# CircuitoControle.net
KiCad netlist of a schematic drawn in Altium Designer
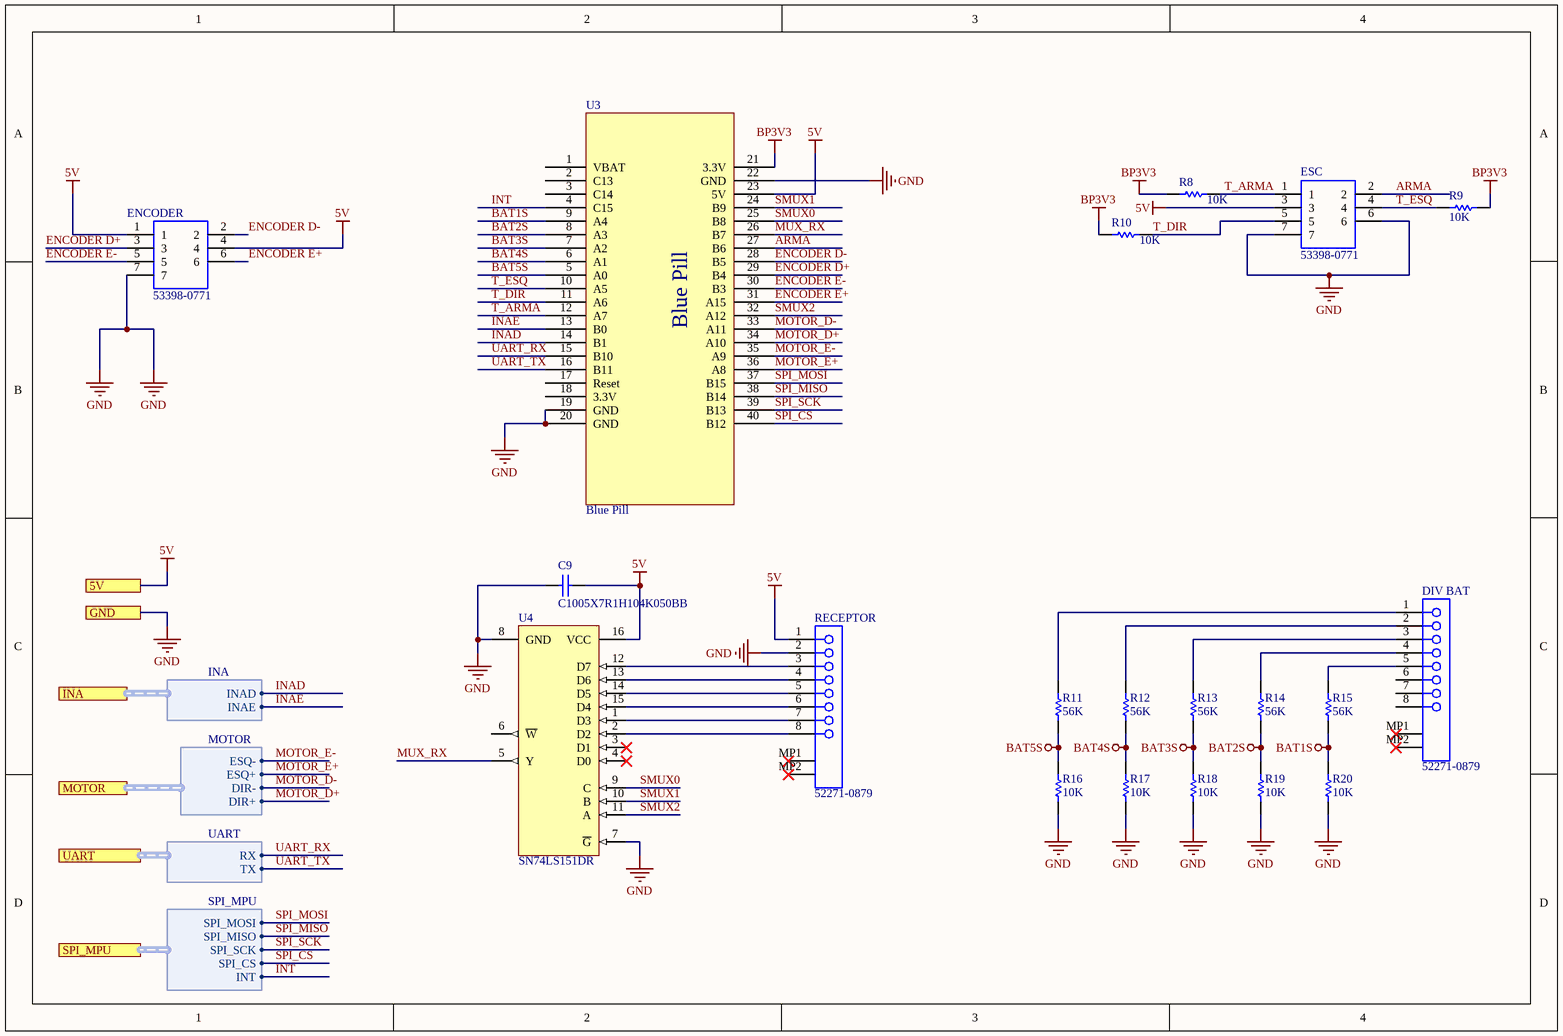
[diagram p0: CircuitoControle.SchDoc]

(export (version "E")
  (design (tool "Eeschema 10.0.6"))
  (components
    (comp (ref "C9")
      (value "C1005X7R1H104K050BB")
      (footprint "TDK-C1005-2_M")
      (description "Chip Capacitor, 0.1 uF, +/- 10%, 50 V, -55 to 125 degC, 0402(1005 Metric), RoHS, Tape and Reel")
      (fields
        (field (name "PCN PART NUMBER") "MLCCPartNumberChange30/Nov/2012")
        (field (name "TOLERANCE") "±10%")
      )
      (libsource (lib "Altium Content Vault") (part "CAP-NP-2"))
    )
    (comp (ref "DIV BAT")
      (value "52271-0879")
      (footprint "MOLX-52271-0879")
      (fields (field (name "MANUFACTURER") "Molex"))
      (libsource (lib "Altium Content Vault") (part "MOLX-52271-0879"))
    )
    (comp (ref "ENCODER")
      (value "53398-0771")
      (footprint "53398-0771:53398-0771")
      (fields (field (name "RS PART NUMBER") "5427220P"))
      (libsource (lib "53398-0771") (part "53398-0771"))
    )
    (comp (ref "ESC")
      (value "53398-0771")
      (footprint "53398-0771")
      (fields (field (name "RS PART NUMBER") "5427220P"))
      (libsource (lib "53398-0771") (part "53398-0771"))
    )
    (comp (ref "R8")
      (value "10K")
      (footprint "RESC0402(1005)_L")
      (description "10K 0.063W 1% 0402 (1005 Metric)  SMD")
      (fields (field (name "TOLERANCE") "1 %") (field (name "POWER") "0.063 W"))
      (libsource (lib "Resistor 0402 10K") (part "CMP-1011-00623-1"))
    )
    (comp (ref "R9")
      (value "10K")
      (footprint "RESC0402(1005)_L")
      (description "10K 0.063W 1% 0402 (1005 Metric)  SMD")
      (fields (field (name "TOLERANCE") "1 %") (field (name "POWER") "0.063 W"))
      (libsource (lib "Resistor 0402 10K") (part "CMP-1011-00623-1"))
    )
    (comp (ref "R10")
      (value "10K")
      (footprint "RESC0402(1005)_L")
      (description "10K 0.063W 1% 0402 (1005 Metric)  SMD")
      (fields (field (name "TOLERANCE") "1 %") (field (name "POWER") "0.063 W"))
      (libsource (lib "Resistor 0402 10K") (part "CMP-1011-00623-1"))
    )
    (comp (ref "R11")
      (value "56K")
      (footprint "RESC0402(1005)_N")
      (description "56K 0.063W 1% 0402 (1005 Metric)  SMD")
      (fields (field (name "TOLERANCE") "1 %") (field (name "POWER") "0.063 W"))
      (libsource (lib "Altium Content Vault") (part "RES"))
    )
    (comp (ref "R12")
      (value "56K")
      (footprint "RESC0402(1005)_N")
      (description "56K 0.063W 1% 0402 (1005 Metric)  SMD")
      (fields (field (name "TOLERANCE") "1 %") (field (name "POWER") "0.063 W"))
      (libsource (lib "Altium Content Vault") (part "RES"))
    )
    (comp (ref "R13")
      (value "56K")
      (footprint "RESC0402(1005)_N")
      (description "56K 0.063W 1% 0402 (1005 Metric)  SMD")
      (fields (field (name "TOLERANCE") "1 %") (field (name "POWER") "0.063 W"))
      (libsource (lib "Altium Content Vault") (part "RES"))
    )
    (comp (ref "R14")
      (value "56K")
      (footprint "RESC0402(1005)_N")
      (description "56K 0.063W 1% 0402 (1005 Metric)  SMD")
      (fields (field (name "TOLERANCE") "1 %") (field (name "POWER") "0.063 W"))
      (libsource (lib "Altium Content Vault") (part "RES"))
    )
    (comp (ref "R15")
      (value "56K")
      (footprint "RESC0402(1005)_N")
      (description "56K 0.063W 1% 0402 (1005 Metric)  SMD")
      (fields (field (name "TOLERANCE") "1 %") (field (name "POWER") "0.063 W"))
      (libsource (lib "Altium Content Vault") (part "RES"))
    )
    (comp (ref "R16")
      (value "10K")
      (footprint "RESC0402(1005)_L")
      (description "10K 0.063W 1% 0402 (1005 Metric)  SMD")
      (fields (field (name "TOLERANCE") "1 %") (field (name "POWER") "0.063 W"))
      (libsource (lib "Resistor 0402 10K") (part "CMP-1011-00623-1"))
    )
    (comp (ref "R17")
      (value "10K")
      (footprint "RESC0402(1005)_L")
      (description "10K 0.063W 1% 0402 (1005 Metric)  SMD")
      (fields (field (name "TOLERANCE") "1 %") (field (name "POWER") "0.063 W"))
      (libsource (lib "Resistor 0402 10K") (part "CMP-1011-00623-1"))
    )
    (comp (ref "R18")
      (value "10K")
      (footprint "RESC0402(1005)_L")
      (description "10K 0.063W 1% 0402 (1005 Metric)  SMD")
      (fields (field (name "TOLERANCE") "1 %") (field (name "POWER") "0.063 W"))
      (libsource (lib "Resistor 0402 10K") (part "CMP-1011-00623-1"))
    )
    (comp (ref "R19")
      (value "10K")
      (footprint "RESC0402(1005)_L")
      (description "10K 0.063W 1% 0402 (1005 Metric)  SMD")
      (fields (field (name "TOLERANCE") "1 %") (field (name "POWER") "0.063 W"))
      (libsource (lib "Resistor 0402 10K") (part "CMP-1011-00623-1"))
    )
    (comp (ref "R20")
      (value "10K")
      (footprint "RESC0402(1005)_L")
      (description "10K 0.063W 1% 0402 (1005 Metric)  SMD")
      (fields (field (name "TOLERANCE") "1 %") (field (name "POWER") "0.063 W"))
      (libsource (lib "Resistor 0402 10K") (part "CMP-1011-00623-1"))
    )
    (comp (ref "RECEPTOR")
      (value "52271-0879")
      (footprint "MOLX-52271-0879")
      (fields (field (name "MANUFACTURER") "Molex"))
      (libsource (lib "Altium Content Vault") (part "MOLX-52271-0879"))
    )
    (comp (ref "U3")
      (value "Blue Pill")
      (footprint "sAMACsYS:blue pill")
      (libsource (lib "Schlib1") (part "Blue Pill"))
    )
    (comp (ref "U4")
      (value "SN74LS151DR")
      (footprint "D0016A_L")
      (description "8-Line To 1-Line Data Selectors/Multiplexers, D0016A, LARGE T&R")
      (fields
        (field (name "MANUFACTURER") "Texas Instruments")
        (field (name "GENERIC PART NUMBER") "SN74LS151")
      )
      (libsource (lib "mux SN74LS151DR") (part "CMP-1633-00148-1"))
    )
  )
  (nets
    (net (code "6") (name "/ARMA") (class "Default")
      (node (ref "ESC") (pin "2") (pinfunction "2_2") (pintype "passive"))
      (node (ref "U3") (pin "27") (pinfunction "B6_27") (pintype "passive"))
    )
    (net (code "7") (name "/ENCODER D+") (class "Default")
      (node (ref "ENCODER") (pin "3") (pinfunction "3_3") (pintype "passive"))
      (node (ref "U3") (pin "29") (pinfunction "B4_29") (pintype "passive"))
    )
    (net (code "8") (name "/ENCODER D-") (class "Default")
      (node (ref "ENCODER") (pin "2") (pinfunction "2_2") (pintype "passive"))
      (node (ref "U3") (pin "28") (pinfunction "B5_28") (pintype "passive"))
    )
    (net (code "9") (name "/ENCODER E+") (class "Default")
      (node (ref "ENCODER") (pin "6") (pinfunction "6_6") (pintype "passive"))
      (node (ref "U3") (pin "31") (pinfunction "A15_31") (pintype "passive"))
    )
    (net (code "10") (name "/ENCODER E-") (class "Default")
      (node (ref "ENCODER") (pin "5") (pinfunction "5_5") (pintype "passive"))
      (node (ref "U3") (pin "30") (pinfunction "B3_30") (pintype "passive"))
    )
    (net (code "11") (name "/INAD") (class "Default")
      (node (ref "U3") (pin "14") (pinfunction "B1_14") (pintype "passive"))
    )
    (net (code "12") (name "/INAE") (class "Default")
      (node (ref "U3") (pin "13") (pinfunction "B0_13") (pintype "passive"))
    )
    (net (code "13") (name "/INT") (class "Default")
      (node (ref "U3") (pin "4") (pinfunction "C15_4") (pintype "passive"))
    )
    (net (code "14") (name "/MOTOR_D+") (class "Default")
      (node (ref "U3") (pin "34") (pinfunction "A10_34") (pintype "passive"))
    )
    (net (code "15") (name "/MOTOR_D-") (class "Default")
      (node (ref "U3") (pin "33") (pinfunction "A11_33") (pintype "passive"))
    )
    (net (code "16") (name "/MOTOR_E+") (class "Default")
      (node (ref "U3") (pin "36") (pinfunction "A8_36") (pintype "passive"))
    )
    (net (code "17") (name "/MOTOR_E-") (class "Default")
      (node (ref "U3") (pin "35") (pinfunction "A9_35") (pintype "passive"))
    )
    (net (code "18") (name "/MUX_RX") (class "Default")
      (node (ref "U3") (pin "26") (pinfunction "B7_26") (pintype "passive"))
      (node (ref "U4") (pin "5") (pinfunction "Y_5") (pintype "output"))
    )
    (net (code "19") (name "/SMUX0") (class "Default")
      (node (ref "U3") (pin "25") (pinfunction "B8_25") (pintype "passive"))
      (node (ref "U4") (pin "9") (pinfunction "C_9") (pintype "input"))
    )
    (net (code "20") (name "/SMUX1") (class "Default")
      (node (ref "U3") (pin "24") (pinfunction "B9_24") (pintype "passive"))
      (node (ref "U4") (pin "10") (pinfunction "B_10") (pintype "input"))
    )
    (net (code "21") (name "/SMUX2") (class "Default")
      (node (ref "U3") (pin "32") (pinfunction "A12_32") (pintype "passive"))
      (node (ref "U4") (pin "11") (pinfunction "A_11") (pintype "input"))
    )
    (net (code "22") (name "/SPI_CS") (class "Default")
      (node (ref "U3") (pin "40") (pinfunction "B12_40") (pintype "passive"))
    )
    (net (code "23") (name "/SPI_MISO") (class "Default")
      (node (ref "U3") (pin "38") (pinfunction "B14_38") (pintype "passive"))
    )
    (net (code "24") (name "/SPI_MOSI") (class "Default")
      (node (ref "U3") (pin "37") (pinfunction "B15_37") (pintype "passive"))
    )
    (net (code "25") (name "/SPI_SCK") (class "Default")
      (node (ref "U3") (pin "39") (pinfunction "B13_39") (pintype "passive"))
    )
    (net (code "26") (name "/T_ARMA") (class "Default")
      (node (ref "ESC") (pin "1") (pinfunction "1_1") (pintype "passive"))
      (node (ref "R8") (pin "1") (pinfunction "1_1") (pintype "passive"))
      (node (ref "U3") (pin "12") (pinfunction "A7_12") (pintype "passive"))
    )
    (net (code "27") (name "/T_DIR") (class "Default")
      (node (ref "ESC") (pin "5") (pinfunction "5_5") (pintype "passive"))
      (node (ref "R10") (pin "1") (pinfunction "1_1") (pintype "passive"))
      (node (ref "U3") (pin "11") (pinfunction "A6_11") (pintype "passive"))
    )
    (net (code "28") (name "/T_ESQ") (class "Default")
      (node (ref "ESC") (pin "4") (pinfunction "4_4") (pintype "passive"))
      (node (ref "R9") (pin "2") (pinfunction "2_2") (pintype "passive"))
      (node (ref "U3") (pin "10") (pinfunction "A5_10") (pintype "passive"))
    )
    (net (code "29") (name "/UART_RX") (class "Default")
      (node (ref "U3") (pin "15") (pinfunction "B10_15") (pintype "passive"))
    )
    (net (code "30") (name "/UART_TX") (class "Default")
      (node (ref "U3") (pin "16") (pinfunction "B11_16") (pintype "passive"))
    )
    (net (code "35") (name "5V") (class "Default")
      (node (ref "C9") (pin "2") (pinfunction "2_2") (pintype "passive"))
      (node (ref "ENCODER") (pin "1") (pinfunction "1_1") (pintype "passive"))
      (node (ref "ENCODER") (pin "4") (pinfunction "4_4") (pintype "passive"))
      (node (ref "ESC") (pin "3") (pinfunction "3_3") (pintype "passive"))
      (node (ref "RECEPTOR") (pin "1") (pinfunction "1_1") (pintype "passive"))
      (node (ref "U3") (pin "23") (pinfunction "5V_23") (pintype "passive"))
      (node (ref "U4") (pin "16") (pinfunction "VCC_16") (pintype "power_in"))
    )
    (net (code "36") (name "BAT1S") (class "Default")
      (node (ref "R15") (pin "1") (pinfunction "1_1") (pintype "passive"))
      (node (ref "R20") (pin "2") (pinfunction "2_2") (pintype "passive"))
      (node (ref "U3") (pin "9") (pinfunction "A4_9") (pintype "passive"))
    )
    (net (code "37") (name "BAT2S") (class "Default")
      (node (ref "R14") (pin "1") (pinfunction "1_1") (pintype "passive"))
      (node (ref "R19") (pin "2") (pinfunction "2_2") (pintype "passive"))
      (node (ref "U3") (pin "8") (pinfunction "A3_8") (pintype "passive"))
    )
    (net (code "38") (name "BAT3S") (class "Default")
      (node (ref "R13") (pin "1") (pinfunction "1_1") (pintype "passive"))
      (node (ref "R18") (pin "2") (pinfunction "2_2") (pintype "passive"))
      (node (ref "U3") (pin "7") (pinfunction "A2_7") (pintype "passive"))
    )
    (net (code "39") (name "BAT4S") (class "Default")
      (node (ref "R12") (pin "1") (pinfunction "1_1") (pintype "passive"))
      (node (ref "R17") (pin "2") (pinfunction "2_2") (pintype "passive"))
      (node (ref "U3") (pin "6") (pinfunction "A1_6") (pintype "passive"))
    )
    (net (code "40") (name "BAT5S") (class "Default")
      (node (ref "R11") (pin "1") (pinfunction "1_1") (pintype "passive"))
      (node (ref "R16") (pin "2") (pinfunction "2_2") (pintype "passive"))
      (node (ref "U3") (pin "5") (pinfunction "A0_5") (pintype "passive"))
    )
    (net (code "41") (name "BP3V3") (class "Default")
      (node (ref "R10") (pin "2") (pinfunction "2_2") (pintype "passive"))
      (node (ref "R8") (pin "2") (pinfunction "2_2") (pintype "passive"))
      (node (ref "R9") (pin "1") (pinfunction "1_1") (pintype "passive"))
      (node (ref "U3") (pin "21") (pinfunction "3.3V_21") (pintype "passive"))
    )
    (net (code "42") (name "GND") (class "Default")
      (node (ref "C9") (pin "1") (pinfunction "1_1") (pintype "passive"))
      (node (ref "ENCODER") (pin "7") (pinfunction "7_7") (pintype "passive"))
      (node (ref "ESC") (pin "6") (pinfunction "6_6") (pintype "passive"))
      (node (ref "ESC") (pin "7") (pinfunction "7_7") (pintype "passive"))
      (node (ref "R16") (pin "1") (pinfunction "1_1") (pintype "passive"))
      (node (ref "R17") (pin "1") (pinfunction "1_1") (pintype "passive"))
      (node (ref "R18") (pin "1") (pinfunction "1_1") (pintype "passive"))
      (node (ref "R19") (pin "1") (pinfunction "1_1") (pintype "passive"))
      (node (ref "R20") (pin "1") (pinfunction "1_1") (pintype "passive"))
      (node (ref "RECEPTOR") (pin "2") (pinfunction "2_2") (pintype "passive"))
      (node (ref "U3") (pin "19") (pinfunction "GND_19") (pintype "passive"))
      (node (ref "U3") (pin "20") (pinfunction "GND_20") (pintype "passive"))
      (node (ref "U3") (pin "22") (pinfunction "GND_22") (pintype "passive"))
      (node (ref "U4") (pin "7") (pinfunction "~{G}_7") (pintype "input"))
      (node (ref "U4") (pin "8") (pinfunction "GND_8") (pintype "power_in"))
    )
    (net (code "43") (name "Net-(DIV BAT-Pad1)") (class "Default")
      (node (ref "DIV BAT") (pin "1") (pinfunction "1_1") (pintype "passive"))
      (node (ref "R11") (pin "2") (pinfunction "2_2") (pintype "passive"))
    )
    (net (code "44") (name "Net-(DIV BAT-Pad2)") (class "Default")
      (node (ref "DIV BAT") (pin "2") (pinfunction "2_2") (pintype "passive"))
      (node (ref "R12") (pin "2") (pinfunction "2_2") (pintype "passive"))
    )
    (net (code "45") (name "Net-(DIV BAT-Pad3)") (class "Default")
      (node (ref "DIV BAT") (pin "3") (pinfunction "3_3") (pintype "passive"))
      (node (ref "R13") (pin "2") (pinfunction "2_2") (pintype "passive"))
    )
    (net (code "46") (name "Net-(DIV BAT-Pad4)") (class "Default")
      (node (ref "DIV BAT") (pin "4") (pinfunction "4_4") (pintype "passive"))
      (node (ref "R14") (pin "2") (pinfunction "2_2") (pintype "passive"))
    )
    (net (code "47") (name "Net-(DIV BAT-Pad5)") (class "Default")
      (node (ref "DIV BAT") (pin "5") (pinfunction "5_5") (pintype "passive"))
      (node (ref "R15") (pin "2") (pinfunction "2_2") (pintype "passive"))
    )
    (net (code "48") (name "Net-(U4-D2)") (class "Default")
      (node (ref "RECEPTOR") (pin "8") (pinfunction "8_8") (pintype "passive"))
      (node (ref "U4") (pin "2") (pinfunction "D2_2") (pintype "input"))
    )
    (net (code "49") (name "Net-(U4-D3)") (class "Default")
      (node (ref "RECEPTOR") (pin "7") (pinfunction "7_7") (pintype "passive"))
      (node (ref "U4") (pin "1") (pinfunction "D3_1") (pintype "input"))
    )
    (net (code "50") (name "Net-(U4-D4)") (class "Default")
      (node (ref "RECEPTOR") (pin "6") (pinfunction "6_6") (pintype "passive"))
      (node (ref "U4") (pin "15") (pinfunction "D4_15") (pintype "input"))
    )
    (net (code "51") (name "Net-(U4-D5)") (class "Default")
      (node (ref "RECEPTOR") (pin "5") (pinfunction "5_5") (pintype "passive"))
      (node (ref "U4") (pin "14") (pinfunction "D5_14") (pintype "input"))
    )
    (net (code "52") (name "Net-(U4-D6)") (class "Default")
      (node (ref "RECEPTOR") (pin "4") (pinfunction "4_4") (pintype "passive"))
      (node (ref "U4") (pin "13") (pinfunction "D6_13") (pintype "input"))
    )
    (net (code "53") (name "Net-(U4-D7)") (class "Default")
      (node (ref "RECEPTOR") (pin "3") (pinfunction "3_3") (pintype "passive"))
      (node (ref "U4") (pin "12") (pinfunction "D7_12") (pintype "input"))
    )
    (net (code "54") (name "unconnected-(DIV BAT-Pad6)") (class "Default")
      (node (ref "DIV BAT") (pin "6") (pinfunction "6_6") (pintype "passive"))
    )
    (net (code "55") (name "unconnected-(DIV BAT-Pad7)") (class "Default")
      (node (ref "DIV BAT") (pin "7") (pinfunction "7_7") (pintype "passive"))
    )
    (net (code "56") (name "unconnected-(DIV BAT-Pad8)") (class "Default")
      (node (ref "DIV BAT") (pin "8") (pinfunction "8_8") (pintype "passive"))
    )
    (net (code "57") (name "unconnected-(DIV BAT-PadMP1)") (class "Default")
      (node (ref "DIV BAT") (pin "MP1") (pinfunction "MP1_MP1") (pintype "passive+no_connect"))
    )
    (net (code "58") (name "unconnected-(DIV BAT-PadMP2)") (class "Default")
      (node (ref "DIV BAT") (pin "MP2") (pinfunction "MP2_MP2") (pintype "passive+no_connect"))
    )
    (net (code "59") (name "unconnected-(RECEPTOR-PadMP1)") (class "Default")
      (node (ref "RECEPTOR") (pin "MP1") (pinfunction "MP1_MP1") (pintype "passive+no_connect"))
    )
    (net (code "60") (name "unconnected-(RECEPTOR-PadMP2)") (class "Default")
      (node (ref "RECEPTOR") (pin "MP2") (pinfunction "MP2_MP2") (pintype "passive+no_connect"))
    )
    (net (code "61") (name "unconnected-(U3-3.3V-Pad18)") (class "Default")
      (node (ref "U3") (pin "18") (pinfunction "3.3V_18") (pintype "passive"))
    )
    (net (code "62") (name "unconnected-(U3-C13-Pad2)") (class "Default")
      (node (ref "U3") (pin "2") (pinfunction "C13_2") (pintype "passive"))
    )
    (net (code "63") (name "unconnected-(U3-C14-Pad3)") (class "Default")
      (node (ref "U3") (pin "3") (pinfunction "C14_3") (pintype "passive"))
    )
    (net (code "64") (name "unconnected-(U3-Reset-Pad17)") (class "Default")
      (node (ref "U3") (pin "17") (pinfunction "Reset_17") (pintype "passive"))
    )
    (net (code "65") (name "unconnected-(U3-VBAT-Pad1)") (class "Default")
      (node (ref "U3") (pin "1") (pinfunction "VBAT_1") (pintype "passive"))
    )
    (net (code "66") (name "unconnected-(U4-D0-Pad4)") (class "Default")
      (node (ref "U4") (pin "4") (pinfunction "D0_4") (pintype "input+no_connect"))
    )
    (net (code "67") (name "unconnected-(U4-D1-Pad3)") (class "Default")
      (node (ref "U4") (pin "3") (pinfunction "D1_3") (pintype "input+no_connect"))
    )
    (net (code "68") (name "unconnected-(U4-~{W}-Pad6)") (class "Default")
      (node (ref "U4") (pin "6") (pinfunction "~{W}_6") (pintype "output"))
    )
  )
)
